# LB-BIT-i1-slideSwitch-v02_rev1.net
KiCad netlist of a schematic drawn in EAGLE
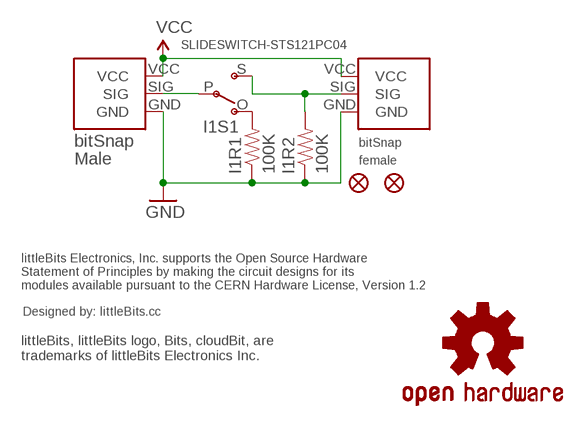
[diagram p0: schematic, sheet 1]

(export (version "E")
  (design (tool "Eeschema 10.0.6"))
  (components
    (comp (ref "I1BSF")
      (value "BITSNAP_FEMALE")
      (footprint "eagle-import:BITSNAP_FEMALE")
      (libsource (lib "eagle-import") (part "BITSNAP_FEMALE"))
    )
    (comp (ref "I1BSM")
      (value "BITSNAP_MALE")
      (footprint "eagle-import:BITSNAP_MALE")
      (libsource (lib "eagle-import") (part "BITSNAP_MALE"))
    )
    (comp (ref "I1FD1")
      (value "FIDUCIAL1X2")
      (footprint "eagle-import:FIDUCIAL-1X2")
      (libsource (lib "eagle-import") (part "FIDUCIAL1X2"))
    )
    (comp (ref "I1FD2")
      (value "FIDUCIAL1X2")
      (footprint "eagle-import:FIDUCIAL-1X2")
      (libsource (lib "eagle-import") (part "FIDUCIAL1X2"))
    )
    (comp (ref "I1R1")
      (value "100K")
      (footprint "eagle-import:0603-RES")
      (libsource (lib "eagle-import") (part "RESISTOR0603-RES"))
    )
    (comp (ref "I1R2")
      (value "100K")
      (footprint "eagle-import:0603-RES")
      (libsource (lib "eagle-import") (part "RESISTOR0603-RES"))
    )
    (comp (ref "I1S1")
      (value "SLIDESWITCH-STS121PC04")
      (footprint "eagle-import:SLIDESWITCH-STS121PC04")
      (libsource (lib "eagle-import") (part "SLIDESWITCH-STS121PC04"))
    )
    (comp (ref "U$1")
      (value "OSHWCREDIT")
      (footprint "eagle-import:OSHWCREDIT")
      (libsource (lib "eagle-import") (part "OSHWCREDIT"))
    )
    (comp (ref "U$2")
      (value "OSHW-LOGOS")
      (footprint "eagle-import:OSHW-LOGO-S")
      (libsource (lib "eagle-import") (part "OSHW-LOGOS"))
    )
  )
  (nets
    (net (code "1") (name "GND") (class "Default")
      (node (ref "I1BSF") (pin "GND") (pinfunction "GND_GND") (pintype "bidirectional"))
      (node (ref "I1BSM") (pin "GND") (pinfunction "GND_GND") (pintype "bidirectional"))
      (node (ref "I1R1") (pin "1") (pinfunction "1_1") (pintype "passive"))
      (node (ref "I1R2") (pin "1") (pinfunction "1_1") (pintype "passive"))
    )
    (net (code "2") (name "Net-(I1BSF-PadSIG)") (class "Default")
      (node (ref "I1BSF") (pin "SIG") (pinfunction "SIG_SIG") (pintype "bidirectional"))
      (node (ref "I1R2") (pin "2") (pinfunction "2_2") (pintype "passive"))
      (node (ref "I1S1") (pin "S") (pinfunction "S_S") (pintype "passive"))
    )
    (net (code "3") (name "Net-(I1BSM-PadSIG)") (class "Default")
      (node (ref "I1BSM") (pin "SIG") (pinfunction "SIG_SIG") (pintype "bidirectional"))
      (node (ref "I1S1") (pin "P") (pinfunction "P_P") (pintype "passive"))
    )
    (net (code "4") (name "Net-(I1R1-Pad2)") (class "Default")
      (node (ref "I1R1") (pin "2") (pinfunction "2_2") (pintype "passive"))
      (node (ref "I1S1") (pin "O") (pinfunction "O_O") (pintype "passive"))
    )
    (net (code "5") (name "VCC") (class "Default")
      (node (ref "I1BSF") (pin "VCC") (pinfunction "VCC_VCC") (pintype "bidirectional"))
      (node (ref "I1BSM") (pin "VCC") (pinfunction "VCC_VCC") (pintype "bidirectional"))
    )
  )
)
